# dualKatana.net
KiCad netlist of a schematic drawn in EAGLE
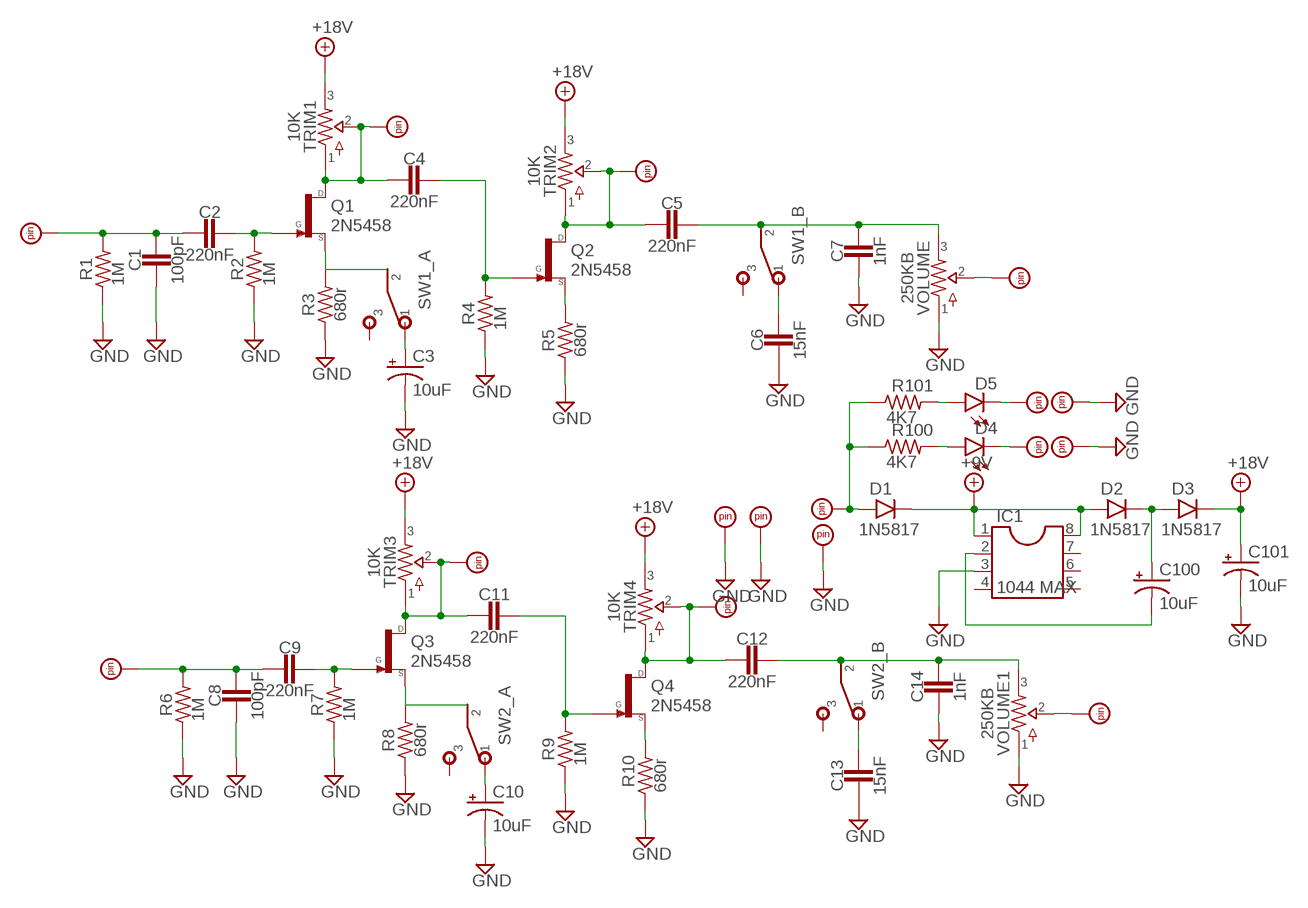
[diagram p0: schematic, sheet 1]

(export (version "E")
  (design (tool "Eeschema 10.0.6"))
  (components
    (comp (ref "C1")
      (value "100pF")
      (footprint "eagle-import:0.2_.MED")
      (libsource (lib "eagle-import") (part "CAP.3"))
    )
    (comp (ref "C2")
      (value "220nF")
      (footprint "eagle-import:0.2_.MED")
      (libsource (lib "eagle-import") (part "CAP.3"))
    )
    (comp (ref "C3")
      (value "10uF")
      (footprint "eagle-import:050_020_1")
      (libsource (lib "eagle-import") (part "0501"))
    )
    (comp (ref "C4")
      (value "220nF")
      (footprint "eagle-import:0.2_.MED")
      (libsource (lib "eagle-import") (part "CAP.3"))
    )
    (comp (ref "C5")
      (value "220nF")
      (footprint "eagle-import:0.2_.MED")
      (libsource (lib "eagle-import") (part "CAP.3"))
    )
    (comp (ref "C6")
      (value "15nF")
      (footprint "eagle-import:0.2_.MED")
      (libsource (lib "eagle-import") (part "CAP.3"))
    )
    (comp (ref "C7")
      (value "1nF")
      (footprint "eagle-import:0.2_.MED")
      (libsource (lib "eagle-import") (part "CAP.3"))
    )
    (comp (ref "C8")
      (value "100pF")
      (footprint "eagle-import:0.2_.MED")
      (libsource (lib "eagle-import") (part "CAP.3"))
    )
    (comp (ref "C9")
      (value "220nF")
      (footprint "eagle-import:0.2_.MED")
      (libsource (lib "eagle-import") (part "CAP.3"))
    )
    (comp (ref "C10")
      (value "10uF")
      (footprint "eagle-import:050_020_1")
      (libsource (lib "eagle-import") (part "0501"))
    )
    (comp (ref "C11")
      (value "220nF")
      (footprint "eagle-import:0.2_.MED")
      (libsource (lib "eagle-import") (part "CAP.3"))
    )
    (comp (ref "C12")
      (value "220nF")
      (footprint "eagle-import:0.2_.MED")
      (libsource (lib "eagle-import") (part "CAP.3"))
    )
    (comp (ref "C13")
      (value "15nF")
      (footprint "eagle-import:0.2_.MED")
      (libsource (lib "eagle-import") (part "CAP.3"))
    )
    (comp (ref "C14")
      (value "1nF")
      (footprint "eagle-import:0.2_.MED")
      (libsource (lib "eagle-import") (part "CAP.3"))
    )
    (comp (ref "C100")
      (value "10uF")
      (footprint "eagle-import:050_020_1")
      (libsource (lib "eagle-import") (part "0501"))
    )
    (comp (ref "C101")
      (value "10uF")
      (footprint "eagle-import:050_020_1")
      (libsource (lib "eagle-import") (part "0501"))
    )
    (comp (ref "D1")
      (value "1N5817")
      (footprint "eagle-import:DO41-3")
      (libsource (lib "eagle-import") (part "DO41.3"))
    )
    (comp (ref "D2")
      (value "1N5817")
      (footprint "eagle-import:DO41-3")
      (libsource (lib "eagle-import") (part "DO41.3"))
    )
    (comp (ref "D3")
      (value "1N5817")
      (footprint "eagle-import:DO41-3")
      (libsource (lib "eagle-import") (part "DO41.3"))
    )
    (comp (ref "D4")
      (value "LED3MM")
      (footprint "eagle-import:LED3MM")
      (libsource (lib "eagle-import") (part "LED3MM"))
    )
    (comp (ref "D5")
      (value "LED3MM")
      (footprint "eagle-import:LED3MM")
      (libsource (lib "eagle-import") (part "LED3MM"))
    )
    (comp (ref "IC1")
      (value "1044 MAX")
      (footprint "eagle-import:DIL08")
      (libsource (lib "eagle-import") (part "DIL8"))
    )
    (comp (ref "Q1")
      (value "2N5458")
      (footprint "eagle-import:TO92")
      (libsource (lib "eagle-import") (part "2N5457"))
    )
    (comp (ref "Q2")
      (value "2N5458")
      (footprint "eagle-import:TO92")
      (libsource (lib "eagle-import") (part "2N5457"))
    )
    (comp (ref "Q3")
      (value "2N5458")
      (footprint "eagle-import:TO92")
      (libsource (lib "eagle-import") (part "2N5457"))
    )
    (comp (ref "Q4")
      (value "2N5458")
      (footprint "eagle-import:TO92")
      (libsource (lib "eagle-import") (part "2N5457"))
    )
    (comp (ref "R1")
      (value "1M")
      (footprint "eagle-import:R0207_3")
      (libsource (lib "eagle-import") (part "RESISTORS.3B"))
    )
    (comp (ref "R2")
      (value "1M")
      (footprint "eagle-import:R0207_3")
      (libsource (lib "eagle-import") (part "RESISTORS.3B"))
    )
    (comp (ref "R3")
      (value "680r")
      (footprint "eagle-import:R0207_3")
      (libsource (lib "eagle-import") (part "RESISTORS.3B"))
    )
    (comp (ref "R4")
      (value "1M")
      (footprint "eagle-import:R0207_3")
      (libsource (lib "eagle-import") (part "RESISTORS.3B"))
    )
    (comp (ref "R5")
      (value "680r")
      (footprint "eagle-import:R0207_3")
      (libsource (lib "eagle-import") (part "RESISTORS.3B"))
    )
    (comp (ref "R6")
      (value "1M")
      (footprint "eagle-import:R0207_3")
      (libsource (lib "eagle-import") (part "RESISTORS.3B"))
    )
    (comp (ref "R7")
      (value "1M")
      (footprint "eagle-import:R0207_3")
      (libsource (lib "eagle-import") (part "RESISTORS.3B"))
    )
    (comp (ref "R8")
      (value "680r")
      (footprint "eagle-import:R0207_3")
      (libsource (lib "eagle-import") (part "RESISTORS.3B"))
    )
    (comp (ref "R9")
      (value "1M")
      (footprint "eagle-import:R0207_3")
      (libsource (lib "eagle-import") (part "RESISTORS.3B"))
    )
    (comp (ref "R10")
      (value "680r")
      (footprint "eagle-import:R0207_3")
      (libsource (lib "eagle-import") (part "RESISTORS.3B"))
    )
    (comp (ref "R100")
      (value "4K7")
      (footprint "eagle-import:R0207_3")
      (libsource (lib "eagle-import") (part "RESISTORS.3B"))
    )
    (comp (ref "R101")
      (value "4K7")
      (footprint "eagle-import:R0207_3")
      (libsource (lib "eagle-import") (part "RESISTORS.3B"))
    )
    (comp (ref "SW1")
      (value "DPDTDPDT_3")
      (footprint "eagle-import:DPDT2_PCB")
      (libsource (lib "eagle-import") (part "DPDTDPDT_3"))
    )
    (comp (ref "SW2")
      (value "DPDTDPDT_3")
      (footprint "eagle-import:DPDT2_PCB")
      (libsource (lib "eagle-import") (part "DPDTDPDT_3"))
    )
    (comp (ref "TRIM1")
      (value "10K")
      (footprint "eagle-import:TRIM3")
      (libsource (lib "eagle-import") (part "TRIMMERTRIM3"))
    )
    (comp (ref "TRIM2")
      (value "10K")
      (footprint "eagle-import:TRIM3")
      (libsource (lib "eagle-import") (part "TRIMMERTRIM3"))
    )
    (comp (ref "TRIM3")
      (value "10K")
      (footprint "eagle-import:TRIM3")
      (libsource (lib "eagle-import") (part "TRIMMERTRIM3"))
    )
    (comp (ref "TRIM4")
      (value "10K")
      (footprint "eagle-import:TRIM3")
      (libsource (lib "eagle-import") (part "TRIMMERTRIM3"))
    )
    (comp (ref "U$1")
      (value "PADS.RND_NL")
      (footprint "eagle-import:PAD2")
      (libsource (lib "eagle-import") (part "PADS.RND_NL"))
    )
    (comp (ref "U$2")
      (value "PADS.RND_NL")
      (footprint "eagle-import:PAD2")
      (libsource (lib "eagle-import") (part "PADS.RND_NL"))
    )
    (comp (ref "U$3")
      (value "PADS.RND_NL")
      (footprint "eagle-import:PAD2")
      (libsource (lib "eagle-import") (part "PADS.RND_NL"))
    )
    (comp (ref "U$4")
      (value "PADS.RND_NL")
      (footprint "eagle-import:PAD2")
      (libsource (lib "eagle-import") (part "PADS.RND_NL"))
    )
    (comp (ref "U$5")
      (value "PADS.RND_NL")
      (footprint "eagle-import:PAD2")
      (libsource (lib "eagle-import") (part "PADS.RND_NL"))
    )
    (comp (ref "U$6")
      (value "PADS.RND_NL")
      (footprint "eagle-import:PAD2")
      (libsource (lib "eagle-import") (part "PADS.RND_NL"))
    )
    (comp (ref "U$7")
      (value "PADS.RND_NL")
      (footprint "eagle-import:PAD2")
      (libsource (lib "eagle-import") (part "PADS.RND_NL"))
    )
    (comp (ref "U$8")
      (value "PADS.RND_NL")
      (footprint "eagle-import:PAD2")
      (libsource (lib "eagle-import") (part "PADS.RND_NL"))
    )
    (comp (ref "U$9")
      (value "PADS.RND_NL")
      (footprint "eagle-import:PAD2")
      (libsource (lib "eagle-import") (part "PADS.RND_NL"))
    )
    (comp (ref "U$10")
      (value "PADS.RND_NL")
      (footprint "eagle-import:PAD2")
      (libsource (lib "eagle-import") (part "PADS.RND_NL"))
    )
    (comp (ref "U$11")
      (value "PADS.RND_NL")
      (footprint "eagle-import:PAD2")
      (libsource (lib "eagle-import") (part "PADS.RND_NL"))
    )
    (comp (ref "U$12")
      (value "PADS.RND_NL")
      (footprint "eagle-import:PAD2")
      (libsource (lib "eagle-import") (part "PADS.RND_NL"))
    )
    (comp (ref "U$13")
      (value "PADS.RND_NL")
      (footprint "eagle-import:PAD2")
      (libsource (lib "eagle-import") (part "PADS.RND_NL"))
    )
    (comp (ref "U$14")
      (value "PADS.RND_NL")
      (footprint "eagle-import:PAD2")
      (libsource (lib "eagle-import") (part "PADS.RND_NL"))
    )
    (comp (ref "U$18")
      (value "PADS.RND_NL")
      (footprint "eagle-import:PAD2")
      (libsource (lib "eagle-import") (part "PADS.RND_NL"))
    )
    (comp (ref "U$19")
      (value "PADS.RND_NL")
      (footprint "eagle-import:PAD2")
      (libsource (lib "eagle-import") (part "PADS.RND_NL"))
    )
    (comp (ref "VOLUME")
      (value "250KB")
      (footprint "eagle-import:16MM_B.MOUNT")
      (libsource (lib "eagle-import") (part "16MM.1"))
    )
    (comp (ref "VOLUME1")
      (value "250KB")
      (footprint "eagle-import:16MM_B.MOUNT")
      (libsource (lib "eagle-import") (part "16MM.1"))
    )
  )
  (nets
    (net (code "1") (name "+9V") (class "Default")
      (node (ref "D1") (pin "C") (pinfunction "C_C") (pintype "passive"))
      (node (ref "D2") (pin "A") (pinfunction "A_A") (pintype "passive"))
      (node (ref "IC1") (pin "1") (pinfunction "1_1") (pintype "passive"))
      (node (ref "IC1") (pin "8") (pinfunction "8_8") (pintype "passive"))
    )
    (net (code "2") (name "+18V") (class "Default")
      (node (ref "C101") (pin "+") (pinfunction "+_+") (pintype "passive"))
      (node (ref "D3") (pin "C") (pinfunction "C_C") (pintype "passive"))
      (node (ref "TRIM1") (pin "3") (pinfunction "3_3") (pintype "passive"))
      (node (ref "TRIM1") (pin "6") (pinfunction "3_6") (pintype "passive"))
      (node (ref "TRIM2") (pin "3") (pinfunction "3_3") (pintype "passive"))
      (node (ref "TRIM2") (pin "6") (pinfunction "3_6") (pintype "passive"))
      (node (ref "TRIM3") (pin "3") (pinfunction "3_3") (pintype "passive"))
      (node (ref "TRIM3") (pin "6") (pinfunction "3_6") (pintype "passive"))
      (node (ref "TRIM4") (pin "3") (pinfunction "3_3") (pintype "passive"))
      (node (ref "TRIM4") (pin "6") (pinfunction "3_6") (pintype "passive"))
    )
    (net (code "3") (name "GND") (class "Default")
      (node (ref "C1") (pin "2") (pinfunction "2_2") (pintype "passive"))
      (node (ref "C10") (pin "-") (pinfunction "-_-") (pintype "passive"))
      (node (ref "C101") (pin "-") (pinfunction "-_-") (pintype "passive"))
      (node (ref "C13") (pin "2") (pinfunction "2_2") (pintype "passive"))
      (node (ref "C14") (pin "2") (pinfunction "2_2") (pintype "passive"))
      (node (ref "C3") (pin "-") (pinfunction "-_-") (pintype "passive"))
      (node (ref "C6") (pin "2") (pinfunction "2_2") (pintype "passive"))
      (node (ref "C7") (pin "2") (pinfunction "2_2") (pintype "passive"))
      (node (ref "C8") (pin "2") (pinfunction "2_2") (pintype "passive"))
      (node (ref "IC1") (pin "3") (pinfunction "3_3") (pintype "passive"))
      (node (ref "R1") (pin "1") (pinfunction "1_1") (pintype "passive"))
      (node (ref "R10") (pin "1") (pinfunction "1_1") (pintype "passive"))
      (node (ref "R2") (pin "1") (pinfunction "1_1") (pintype "passive"))
      (node (ref "R3") (pin "1") (pinfunction "1_1") (pintype "passive"))
      (node (ref "R4") (pin "1") (pinfunction "1_1") (pintype "passive"))
      (node (ref "R5") (pin "1") (pinfunction "1_1") (pintype "passive"))
      (node (ref "R6") (pin "1") (pinfunction "1_1") (pintype "passive"))
      (node (ref "R7") (pin "1") (pinfunction "1_1") (pintype "passive"))
      (node (ref "R8") (pin "1") (pinfunction "1_1") (pintype "passive"))
      (node (ref "R9") (pin "1") (pinfunction "1_1") (pintype "passive"))
      (node (ref "U$18") (pin "P$1") (pinfunction "P$1_P$1") (pintype "bidirectional"))
      (node (ref "U$19") (pin "P$1") (pinfunction "P$1_P$1") (pintype "bidirectional"))
      (node (ref "U$2") (pin "P$1") (pinfunction "P$1_P$1") (pintype "bidirectional"))
      (node (ref "U$5") (pin "P$1") (pinfunction "P$1_P$1") (pintype "bidirectional"))
      (node (ref "U$6") (pin "P$1") (pinfunction "P$1_P$1") (pintype "bidirectional"))
      (node (ref "VOLUME") (pin "1") (pinfunction "1_1") (pintype "passive"))
      (node (ref "VOLUME1") (pin "1") (pinfunction "1_1") (pintype "passive"))
    )
    (net (code "4") (name "Net-(C1-Pad1)") (class "Default")
      (node (ref "C1") (pin "1") (pinfunction "1_1") (pintype "passive"))
      (node (ref "C2") (pin "2") (pinfunction "2_2") (pintype "passive"))
      (node (ref "R1") (pin "2") (pinfunction "2_2") (pintype "passive"))
      (node (ref "U$7") (pin "P$1") (pinfunction "P$1_P$1") (pintype "bidirectional"))
    )
    (net (code "5") (name "Net-(C8-Pad1)") (class "Default")
      (node (ref "C8") (pin "1") (pinfunction "1_1") (pintype "passive"))
      (node (ref "C9") (pin "2") (pinfunction "2_2") (pintype "passive"))
      (node (ref "R6") (pin "2") (pinfunction "2_2") (pintype "passive"))
      (node (ref "U$11") (pin "P$1") (pinfunction "P$1_P$1") (pintype "bidirectional"))
    )
    (net (code "6") (name "Net-(C100-Pad+)") (class "Default")
      (node (ref "C100") (pin "+") (pinfunction "+_+") (pintype "passive"))
      (node (ref "D2") (pin "C") (pinfunction "C_C") (pintype "passive"))
      (node (ref "D3") (pin "A") (pinfunction "A_A") (pintype "passive"))
    )
    (net (code "7") (name "Net-(C100-Pad-)") (class "Default")
      (node (ref "C100") (pin "-") (pinfunction "-_-") (pintype "passive"))
      (node (ref "IC1") (pin "2") (pinfunction "2_2") (pintype "passive"))
    )
    (net (code "8") (name "Net-(D1-PadA)") (class "Default")
      (node (ref "D1") (pin "A") (pinfunction "A_A") (pintype "passive"))
      (node (ref "R100") (pin "1") (pinfunction "1_1") (pintype "passive"))
      (node (ref "R101") (pin "1") (pinfunction "1_1") (pintype "passive"))
      (node (ref "U$1") (pin "P$1") (pinfunction "P$1_P$1") (pintype "bidirectional"))
    )
    (net (code "9") (name "Net-(D4-C)") (class "Default")
      (node (ref "D4") (pin "K") (pinfunction "C_K") (pintype "passive"))
      (node (ref "U$3") (pin "P$1") (pinfunction "P$1_P$1") (pintype "bidirectional"))
    )
    (net (code "10") (name "Net-(D4-PadA)") (class "Default")
      (node (ref "D4") (pin "A") (pinfunction "A_A") (pintype "passive"))
      (node (ref "R100") (pin "2") (pinfunction "2_2") (pintype "passive"))
    )
    (net (code "11") (name "Net-(D5-C)") (class "Default")
      (node (ref "D5") (pin "K") (pinfunction "C_K") (pintype "passive"))
      (node (ref "U$4") (pin "P$1") (pinfunction "P$1_P$1") (pintype "bidirectional"))
    )
    (net (code "12") (name "Net-(D5-PadA)") (class "Default")
      (node (ref "D5") (pin "A") (pinfunction "A_A") (pintype "passive"))
      (node (ref "R101") (pin "2") (pinfunction "2_2") (pintype "passive"))
    )
    (net (code "13") (name "Net-(Q1-D)") (class "Default")
      (node (ref "C4") (pin "2") (pinfunction "2_2") (pintype "passive"))
      (node (ref "Q1") (pin "1") (pinfunction "D_1") (pintype "passive"))
      (node (ref "TRIM1") (pin "1") (pinfunction "1_1") (pintype "passive"))
      (node (ref "TRIM1") (pin "2") (pinfunction "2_2") (pintype "passive"))
      (node (ref "TRIM1") (pin "4") (pinfunction "1_4") (pintype "passive"))
      (node (ref "TRIM1") (pin "5") (pinfunction "2_5") (pintype "passive"))
      (node (ref "U$8") (pin "P$1") (pinfunction "P$1_P$1") (pintype "bidirectional"))
    )
    (net (code "14") (name "Net-(Q1-G)") (class "Default")
      (node (ref "C2") (pin "1") (pinfunction "1_1") (pintype "passive"))
      (node (ref "Q1") (pin "3") (pinfunction "G_3") (pintype "passive"))
      (node (ref "R2") (pin "2") (pinfunction "2_2") (pintype "passive"))
    )
    (net (code "15") (name "Net-(Q1-S)") (class "Default")
      (node (ref "Q1") (pin "2") (pinfunction "S_2") (pintype "passive"))
      (node (ref "R3") (pin "2") (pinfunction "2_2") (pintype "passive"))
      (node (ref "SW1") (pin "A2") (pinfunction "2_A2") (pintype "passive"))
    )
    (net (code "16") (name "Net-(Q2-D)") (class "Default")
      (node (ref "C5") (pin "2") (pinfunction "2_2") (pintype "passive"))
      (node (ref "Q2") (pin "1") (pinfunction "D_1") (pintype "passive"))
      (node (ref "TRIM2") (pin "1") (pinfunction "1_1") (pintype "passive"))
      (node (ref "TRIM2") (pin "2") (pinfunction "2_2") (pintype "passive"))
      (node (ref "TRIM2") (pin "4") (pinfunction "1_4") (pintype "passive"))
      (node (ref "TRIM2") (pin "5") (pinfunction "2_5") (pintype "passive"))
      (node (ref "U$9") (pin "P$1") (pinfunction "P$1_P$1") (pintype "bidirectional"))
    )
    (net (code "17") (name "Net-(Q2-G)") (class "Default")
      (node (ref "C4") (pin "1") (pinfunction "1_1") (pintype "passive"))
      (node (ref "Q2") (pin "3") (pinfunction "G_3") (pintype "passive"))
      (node (ref "R4") (pin "2") (pinfunction "2_2") (pintype "passive"))
    )
    (net (code "18") (name "Net-(Q2-S)") (class "Default")
      (node (ref "Q2") (pin "2") (pinfunction "S_2") (pintype "passive"))
      (node (ref "R5") (pin "2") (pinfunction "2_2") (pintype "passive"))
    )
    (net (code "19") (name "Net-(Q3-D)") (class "Default")
      (node (ref "C11") (pin "2") (pinfunction "2_2") (pintype "passive"))
      (node (ref "Q3") (pin "1") (pinfunction "D_1") (pintype "passive"))
      (node (ref "TRIM3") (pin "1") (pinfunction "1_1") (pintype "passive"))
      (node (ref "TRIM3") (pin "2") (pinfunction "2_2") (pintype "passive"))
      (node (ref "TRIM3") (pin "4") (pinfunction "1_4") (pintype "passive"))
      (node (ref "TRIM3") (pin "5") (pinfunction "2_5") (pintype "passive"))
      (node (ref "U$12") (pin "P$1") (pinfunction "P$1_P$1") (pintype "bidirectional"))
    )
    (net (code "20") (name "Net-(Q3-G)") (class "Default")
      (node (ref "C9") (pin "1") (pinfunction "1_1") (pintype "passive"))
      (node (ref "Q3") (pin "3") (pinfunction "G_3") (pintype "passive"))
      (node (ref "R7") (pin "2") (pinfunction "2_2") (pintype "passive"))
    )
    (net (code "21") (name "Net-(Q3-S)") (class "Default")
      (node (ref "Q3") (pin "2") (pinfunction "S_2") (pintype "passive"))
      (node (ref "R8") (pin "2") (pinfunction "2_2") (pintype "passive"))
      (node (ref "SW2") (pin "A2") (pinfunction "2_A2") (pintype "passive"))
    )
    (net (code "22") (name "Net-(Q4-D)") (class "Default")
      (node (ref "C12") (pin "2") (pinfunction "2_2") (pintype "passive"))
      (node (ref "Q4") (pin "1") (pinfunction "D_1") (pintype "passive"))
      (node (ref "TRIM4") (pin "1") (pinfunction "1_1") (pintype "passive"))
      (node (ref "TRIM4") (pin "2") (pinfunction "2_2") (pintype "passive"))
      (node (ref "TRIM4") (pin "4") (pinfunction "1_4") (pintype "passive"))
      (node (ref "TRIM4") (pin "5") (pinfunction "2_5") (pintype "passive"))
      (node (ref "U$13") (pin "P$1") (pinfunction "P$1_P$1") (pintype "bidirectional"))
    )
    (net (code "23") (name "Net-(Q4-G)") (class "Default")
      (node (ref "C11") (pin "1") (pinfunction "1_1") (pintype "passive"))
      (node (ref "Q4") (pin "3") (pinfunction "G_3") (pintype "passive"))
      (node (ref "R9") (pin "2") (pinfunction "2_2") (pintype "passive"))
    )
    (net (code "24") (name "Net-(Q4-S)") (class "Default")
      (node (ref "Q4") (pin "2") (pinfunction "S_2") (pintype "passive"))
      (node (ref "R10") (pin "2") (pinfunction "2_2") (pintype "passive"))
    )
    (net (code "25") (name "Net-(SW1A-1)") (class "Default")
      (node (ref "C3") (pin "+") (pinfunction "+_+") (pintype "passive"))
      (node (ref "SW1") (pin "A1") (pinfunction "1_A1") (pintype "passive"))
    )
    (net (code "26") (name "Net-(SW1B-1)") (class "Default")
      (node (ref "C6") (pin "1") (pinfunction "1_1") (pintype "passive"))
      (node (ref "SW1") (pin "B1") (pinfunction "1_B1") (pintype "passive"))
    )
    (net (code "27") (name "Net-(SW1B-2)") (class "Default")
      (node (ref "C5") (pin "1") (pinfunction "1_1") (pintype "passive"))
      (node (ref "C7") (pin "1") (pinfunction "1_1") (pintype "passive"))
      (node (ref "SW1") (pin "B2") (pinfunction "2_B2") (pintype "passive"))
      (node (ref "VOLUME") (pin "3") (pinfunction "3_3") (pintype "passive"))
    )
    (net (code "28") (name "Net-(SW2A-1)") (class "Default")
      (node (ref "C10") (pin "+") (pinfunction "+_+") (pintype "passive"))
      (node (ref "SW2") (pin "A1") (pinfunction "1_A1") (pintype "passive"))
    )
    (net (code "29") (name "Net-(SW2B-1)") (class "Default")
      (node (ref "C13") (pin "1") (pinfunction "1_1") (pintype "passive"))
      (node (ref "SW2") (pin "B1") (pinfunction "1_B1") (pintype "passive"))
    )
    (net (code "30") (name "Net-(SW2B-2)") (class "Default")
      (node (ref "C12") (pin "1") (pinfunction "1_1") (pintype "passive"))
      (node (ref "C14") (pin "1") (pinfunction "1_1") (pintype "passive"))
      (node (ref "SW2") (pin "B2") (pinfunction "2_B2") (pintype "passive"))
      (node (ref "VOLUME1") (pin "3") (pinfunction "3_3") (pintype "passive"))
    )
    (net (code "31") (name "Net-(U$10-PadP$1)") (class "Default")
      (node (ref "U$10") (pin "P$1") (pinfunction "P$1_P$1") (pintype "bidirectional"))
      (node (ref "VOLUME") (pin "2") (pinfunction "2_2") (pintype "passive"))
    )
    (net (code "32") (name "Net-(U$14-PadP$1)") (class "Default")
      (node (ref "U$14") (pin "P$1") (pinfunction "P$1_P$1") (pintype "bidirectional"))
      (node (ref "VOLUME1") (pin "2") (pinfunction "2_2") (pintype "passive"))
    )
    (net (code "33") (name "unconnected-(IC1-Pad4)") (class "Default")
      (node (ref "IC1") (pin "4") (pinfunction "4_4") (pintype "passive"))
    )
    (net (code "34") (name "unconnected-(IC1-Pad5)") (class "Default")
      (node (ref "IC1") (pin "5") (pinfunction "5_5") (pintype "passive"))
    )
    (net (code "35") (name "unconnected-(IC1-Pad6)") (class "Default")
      (node (ref "IC1") (pin "6") (pinfunction "6_6") (pintype "passive"))
    )
    (net (code "36") (name "unconnected-(IC1-Pad7)") (class "Default")
      (node (ref "IC1") (pin "7") (pinfunction "7_7") (pintype "passive"))
    )
    (net (code "37") (name "unconnected-(SW1A-3-PadA3)") (class "Default")
      (node (ref "SW1") (pin "A3") (pinfunction "3_A3") (pintype "passive"))
    )
    (net (code "38") (name "unconnected-(SW1B-3-PadB3)") (class "Default")
      (node (ref "SW1") (pin "B3") (pinfunction "3_B3") (pintype "passive"))
    )
    (net (code "39") (name "unconnected-(SW2A-3-PadA3)") (class "Default")
      (node (ref "SW2") (pin "A3") (pinfunction "3_A3") (pintype "passive"))
    )
    (net (code "40") (name "unconnected-(SW2B-3-PadB3)") (class "Default")
      (node (ref "SW2") (pin "B3") (pinfunction "3_B3") (pintype "passive"))
    )
  )
)
